# riscurino-1_0.net
KiCad netlist of a schematic drawn in EAGLE
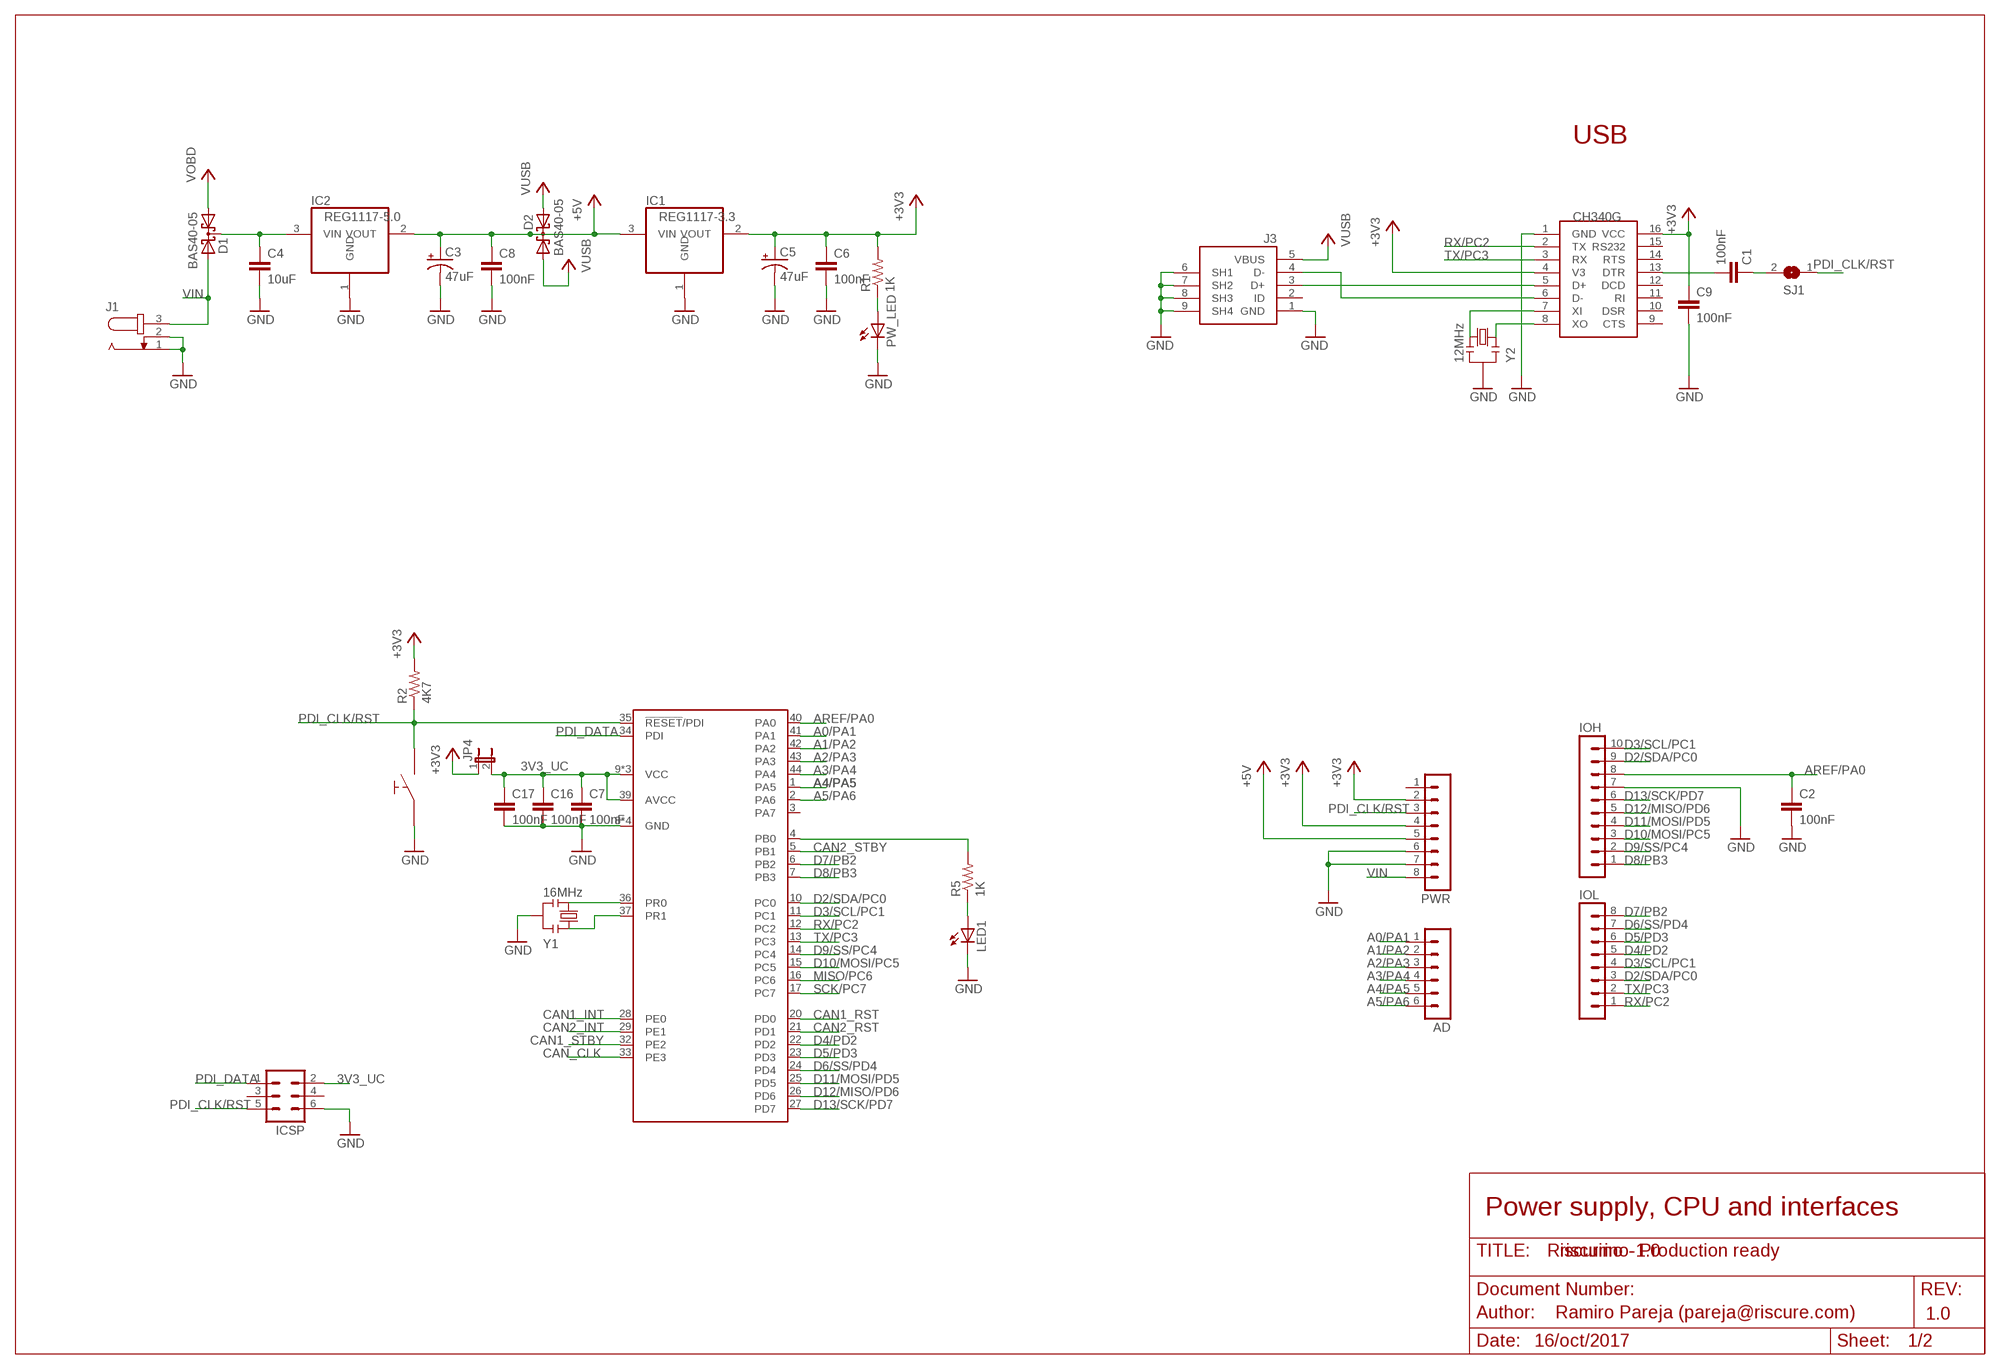
[diagram p0: schematic, sheet 1]
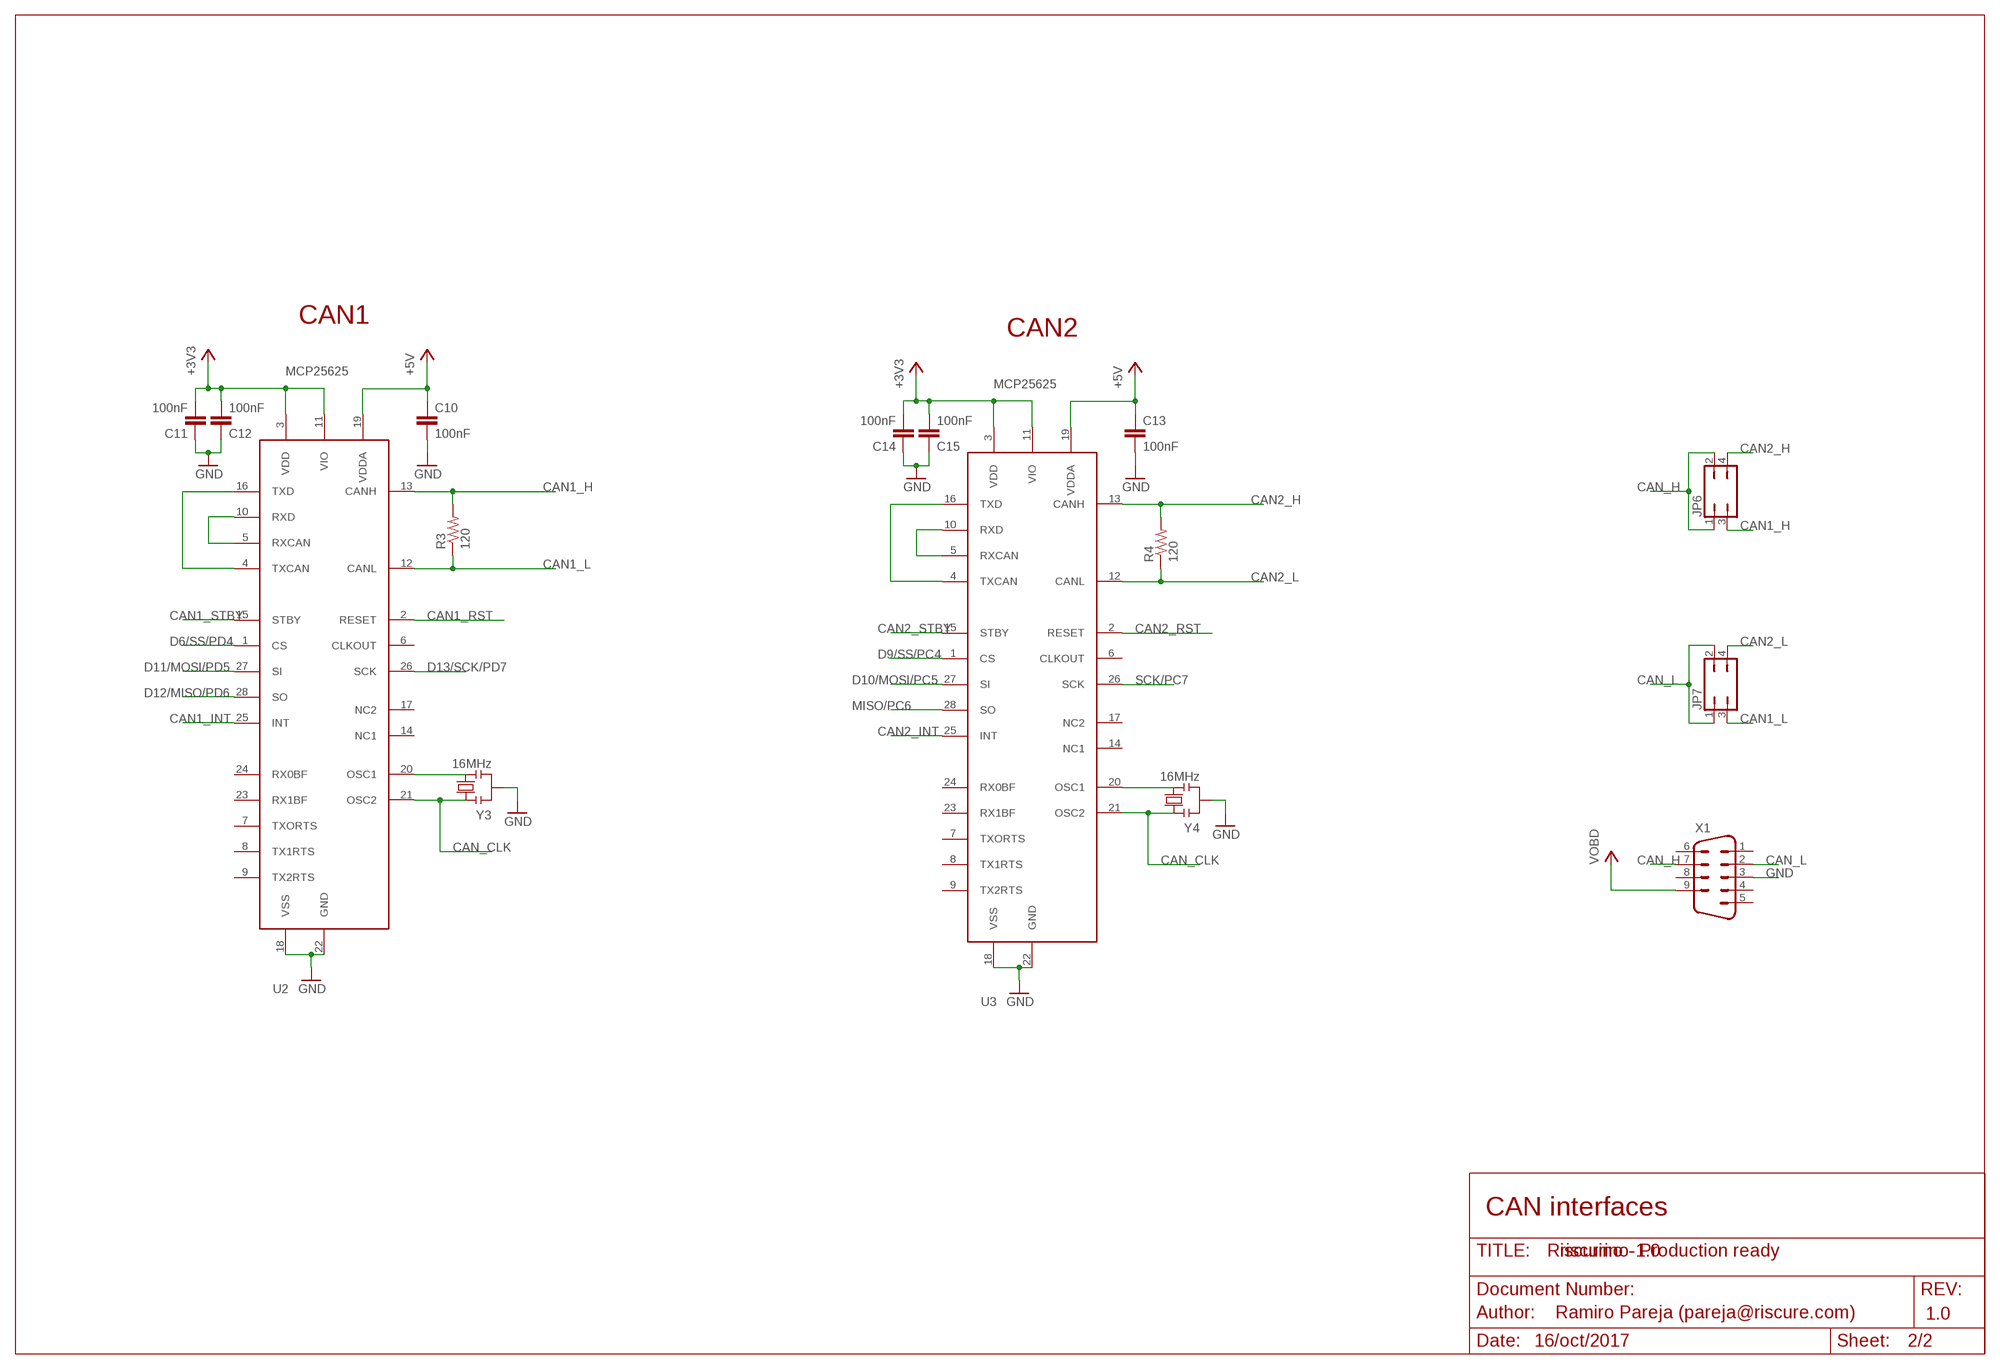
[diagram p1: schematic, sheet 2]

(export (version "E")
  (design (tool "Eeschema 10.0.6"))
  (components
    (comp (ref "AD")
      (value "MA06-1")
      (footprint "eagle-import:MA06-1")
      (libsource (lib "eagle-import") (part "MA06-1"))
    )
    (comp (ref "C1")
      (value "100nF")
      (footprint "eagle-import:C0805")
      (libsource (lib "eagle-import") (part "C-EUC0805"))
    )
    (comp (ref "C2")
      (value "100nF")
      (footprint "eagle-import:C0805")
      (libsource (lib "eagle-import") (part "C-EUC0805"))
    )
    (comp (ref "C3")
      (value "47uF")
      (footprint "eagle-import:PANASONIC_C")
      (libsource (lib "eagle-import") (part "CPOL-USC"))
    )
    (comp (ref "C4")
      (value "10uF")
      (footprint "eagle-import:C0805")
      (libsource (lib "eagle-import") (part "C-EUC0805"))
    )
    (comp (ref "C5")
      (value "47uF")
      (footprint "eagle-import:PANASONIC_C")
      (libsource (lib "eagle-import") (part "CPOL-USC"))
    )
    (comp (ref "C6")
      (value "100nF")
      (footprint "eagle-import:C0805")
      (libsource (lib "eagle-import") (part "C-EUC0805"))
    )
    (comp (ref "C7")
      (value "100nF")
      (footprint "eagle-import:C0805")
      (libsource (lib "eagle-import") (part "C-EUC0805"))
    )
    (comp (ref "C8")
      (value "100nF")
      (footprint "eagle-import:C0805")
      (libsource (lib "eagle-import") (part "C-EUC0805"))
    )
    (comp (ref "C9")
      (value "100nF")
      (footprint "eagle-import:C0805")
      (libsource (lib "eagle-import") (part "C-EUC0805"))
    )
    (comp (ref "C16")
      (value "100nF")
      (footprint "eagle-import:C0805")
      (libsource (lib "eagle-import") (part "C-EUC0805"))
    )
    (comp (ref "C17")
      (value "100nF")
      (footprint "eagle-import:C0805")
      (libsource (lib "eagle-import") (part "C-EUC0805"))
    )
    (comp (ref "D1")
      (value "BAS40-05")
      (footprint "eagle-import:SOT23")
      (libsource (lib "eagle-import") (part "BAS40-05"))
    )
    (comp (ref "D2")
      (value "BAS40-05")
      (footprint "eagle-import:SOT23")
      (libsource (lib "eagle-import") (part "BAS40-05"))
    )
    (comp (ref "IC1")
      (value "REG1117-3.3")
      (footprint "eagle-import:SOT223")
      (fields (field (name "MPN") "REG1117"))
      (libsource (lib "eagle-import") (part "REG1117"))
    )
    (comp (ref "IC2")
      (value "REG1117-5.0")
      (footprint "eagle-import:SOT223")
      (fields (field (name "MPN") "REG1117"))
      (libsource (lib "eagle-import") (part "REG1117"))
    )
    (comp (ref "ICSP")
      (value "MA03-2")
      (footprint "eagle-import:MA03-2")
      (libsource (lib "eagle-import") (part "MA03-2"))
    )
    (comp (ref "IOH")
      (value "MA10-1")
      (footprint "eagle-import:MA10-1")
      (libsource (lib "eagle-import") (part "MA10-1"))
    )
    (comp (ref "IOL")
      (value "MA08-1")
      (footprint "eagle-import:MA08-1")
      (libsource (lib "eagle-import") (part "MA08-1"))
    )
    (comp (ref "J1")
      (value "JACK-PLUG0")
      (footprint "eagle-import:SPC4077")
      (libsource (lib "eagle-import") (part "JACK-PLUG0"))
    )
    (comp (ref "J3")
      (value "0219_14850")
      (footprint "eagle-import:USB-MINI-B_2")
      (fields (field (name "PART_NUMBER") "14850"))
      (libsource (lib "eagle-import") (part "0219_14850"))
    )
    (comp (ref "JP4")
      (value "JP1E")
      (footprint "eagle-import:JP1")
      (libsource (lib "eagle-import") (part "JP1E"))
    )
    (comp (ref "LED1")
      (value "LEDCHIPLED_0805")
      (footprint "eagle-import:CHIPLED_0805")
      (libsource (lib "eagle-import") (part "LEDCHIPLED_0805"))
    )
    (comp (ref "PWR")
      (value "MA08-1")
      (footprint "eagle-import:MA08-1")
      (libsource (lib "eagle-import") (part "MA08-1"))
    )
    (comp (ref "PW_LED")
      (value "LEDCHIPLED_0805")
      (footprint "eagle-import:CHIPLED_0805")
      (libsource (lib "eagle-import") (part "LEDCHIPLED_0805"))
    )
    (comp (ref "R1")
      (value "1K")
      (footprint "eagle-import:R0805")
      (libsource (lib "eagle-import") (part "R-US_R0805"))
    )
    (comp (ref "R2")
      (value "4K7")
      (footprint "eagle-import:R0805")
      (libsource (lib "eagle-import") (part "R-US_R0805"))
    )
    (comp (ref "R5")
      (value "1K")
      (footprint "eagle-import:R0805")
      (libsource (lib "eagle-import") (part "R-US_R0805"))
    )
    (comp (ref "SJ1") (value "SJ") (footprint "eagle-import:SJ") (libsource (lib "eagle-import") (part "SJ")))
    (comp (ref "U$1")
      (value "SWITCH_3X6_BIG")
      (footprint "eagle-import:SWITCH_3X6_BIG")
      (libsource (lib "eagle-import") (part "SWITCH_3X6_BIG"))
    )
    (comp (ref "U1")
      (value "ATXMEGA128A4U-AU")
      (footprint "eagle-import:TQFP-44A-44")
      (libsource (lib "eagle-import") (part "ATXMEGA128A4U-AU"))
    )
    (comp (ref "U4")
      (value "CH340G")
      (footprint "eagle-import:SOIC16")
      (libsource (lib "eagle-import") (part "CH340G"))
    )
    (comp (ref "Y1")
      (value "16MHz")
      (footprint "eagle-import:RESONATOR")
      (fields (field (name "PART_NUMBER") "CSTCE16M0V53-R0"))
      (libsource (lib "eagle-import") (part "0011_CSTCE16M0V53-R0"))
    )
    (comp (ref "Y2")
      (value "12MHz")
      (footprint "eagle-import:RESONATOR")
      (fields (field (name "PART_NUMBER") "CSTCE16M0V53-R0"))
      (libsource (lib "eagle-import") (part "0011_CSTCE16M0V53-R0"))
    )
    (comp (ref "C10")
      (value "100nF")
      (footprint "eagle-import:C0805")
      (libsource (lib "eagle-import") (part "C-EUC0805"))
    )
    (comp (ref "C11")
      (value "100nF")
      (footprint "eagle-import:C0805")
      (libsource (lib "eagle-import") (part "C-EUC0805"))
    )
    (comp (ref "C12")
      (value "100nF")
      (footprint "eagle-import:C0805")
      (libsource (lib "eagle-import") (part "C-EUC0805"))
    )
    (comp (ref "C13")
      (value "100nF")
      (footprint "eagle-import:C0805")
      (libsource (lib "eagle-import") (part "C-EUC0805"))
    )
    (comp (ref "C14")
      (value "100nF")
      (footprint "eagle-import:C0805")
      (libsource (lib "eagle-import") (part "C-EUC0805"))
    )
    (comp (ref "C15")
      (value "100nF")
      (footprint "eagle-import:C0805")
      (libsource (lib "eagle-import") (part "C-EUC0805"))
    )
    (comp (ref "JP6")
      (value "JP2Q")
      (footprint "eagle-import:JP2Q")
      (libsource (lib "eagle-import") (part "JP2Q"))
    )
    (comp (ref "JP7")
      (value "JP2Q")
      (footprint "eagle-import:JP2Q")
      (libsource (lib "eagle-import") (part "JP2Q"))
    )
    (comp (ref "R3")
      (value "120")
      (footprint "eagle-import:R0805")
      (libsource (lib "eagle-import") (part "R-US_R0805"))
    )
    (comp (ref "R4")
      (value "120")
      (footprint "eagle-import:R0805")
      (libsource (lib "eagle-import") (part "R-US_R0805"))
    )
    (comp (ref "U2")
      (value "MCP25625")
      (footprint "eagle-import:QFN28")
      (libsource (lib "eagle-import") (part "MCP25625"))
    )
    (comp (ref "U3")
      (value "MCP25625")
      (footprint "eagle-import:QFN28")
      (libsource (lib "eagle-import") (part "MCP25625"))
    )
    (comp (ref "X1")
      (value "M09HP")
      (footprint "eagle-import:M09HP")
      (libsource (lib "eagle-import") (part "M09HP"))
    )
    (comp (ref "Y3")
      (value "16MHz")
      (footprint "eagle-import:RESONATOR")
      (fields (field (name "PART_NUMBER") "CSTCE16M0V53-R0"))
      (libsource (lib "eagle-import") (part "0011_CSTCE16M0V53-R0"))
    )
    (comp (ref "Y4")
      (value "16MHz")
      (footprint "eagle-import:RESONATOR")
      (fields (field (name "PART_NUMBER") "CSTCE16M0V53-R0"))
      (libsource (lib "eagle-import") (part "0011_CSTCE16M0V53-R0"))
    )
  )
  (nets
    (net (code "1") (name "+3V3") (class "Default")
      (node (ref "C11") (pin "2") (pinfunction "2_2") (pintype "passive"))
      (node (ref "C12") (pin "2") (pinfunction "2_2") (pintype "passive"))
      (node (ref "C14") (pin "2") (pinfunction "2_2") (pintype "passive"))
      (node (ref "C15") (pin "2") (pinfunction "2_2") (pintype "passive"))
      (node (ref "C5") (pin "+") (pinfunction "+_+") (pintype "passive"))
      (node (ref "C6") (pin "1") (pinfunction "1_1") (pintype "passive"))
      (node (ref "C9") (pin "1") (pinfunction "1_1") (pintype "passive"))
      (node (ref "IC1") (pin "2") (pinfunction "VOUT_2") (pintype "output"))
      (node (ref "JP4") (pin "1") (pinfunction "1_1") (pintype "passive"))
      (node (ref "PWR") (pin "2") (pinfunction "2_2") (pintype "passive"))
      (node (ref "PWR") (pin "4") (pinfunction "4_4") (pintype "passive"))
      (node (ref "R1") (pin "2") (pinfunction "2_2") (pintype "passive"))
      (node (ref "R2") (pin "2") (pinfunction "2_2") (pintype "passive"))
      (node (ref "U2") (pin "11") (pinfunction "VIO_11") (pintype "bidirectional"))
      (node (ref "U2") (pin "3") (pinfunction "VDD_3") (pintype "power_in"))
      (node (ref "U3") (pin "11") (pinfunction "VIO_11") (pintype "bidirectional"))
      (node (ref "U3") (pin "3") (pinfunction "VDD_3") (pintype "power_in"))
      (node (ref "U4") (pin "16") (pinfunction "VCC_16") (pintype "bidirectional"))
      (node (ref "U4") (pin "4") (pinfunction "V3_4") (pintype "bidirectional"))
    )
    (net (code "2") (name "+5V") (class "Default")
      (node (ref "C10") (pin "1") (pinfunction "1_1") (pintype "passive"))
      (node (ref "C13") (pin "1") (pinfunction "1_1") (pintype "passive"))
      (node (ref "C3") (pin "+") (pinfunction "+_+") (pintype "passive"))
      (node (ref "C8") (pin "1") (pinfunction "1_1") (pintype "passive"))
      (node (ref "D2") (pin "3") (pinfunction "C_3") (pintype "passive"))
      (node (ref "IC1") (pin "3") (pinfunction "VIN_3") (pintype "input"))
      (node (ref "IC2") (pin "2") (pinfunction "VOUT_2") (pintype "output"))
      (node (ref "PWR") (pin "5") (pinfunction "5_5") (pintype "passive"))
      (node (ref "U2") (pin "19") (pinfunction "VDDA_19") (pintype "power_in"))
      (node (ref "U3") (pin "19") (pinfunction "VDDA_19") (pintype "power_in"))
    )
    (net (code "3") (name "3V3_UC") (class "Default")
      (node (ref "C16") (pin "1") (pinfunction "1_1") (pintype "passive"))
      (node (ref "C17") (pin "1") (pinfunction "1_1") (pintype "passive"))
      (node (ref "C7") (pin "1") (pinfunction "1_1") (pintype "passive"))
      (node (ref "ICSP") (pin "2") (pinfunction "2_2") (pintype "passive"))
      (node (ref "JP4") (pin "2") (pinfunction "2_2") (pintype "passive"))
      (node (ref "U1") (pin "19") (pinfunction "VCC_19") (pintype "power_in"))
      (node (ref "U1") (pin "31") (pinfunction "VCC_31") (pintype "power_in"))
      (node (ref "U1") (pin "39") (pinfunction "AVCC_39") (pintype "power_in"))
      (node (ref "U1") (pin "9") (pinfunction "VCC_9") (pintype "power_in"))
    )
    (net (code "4") (name "A0{slash}PA1") (class "Default")
      (node (ref "AD") (pin "1") (pinfunction "1_1") (pintype "passive"))
      (node (ref "U1") (pin "41") (pinfunction "PA1_41") (pintype "bidirectional"))
    )
    (net (code "5") (name "A1{slash}PA2") (class "Default")
      (node (ref "AD") (pin "2") (pinfunction "2_2") (pintype "passive"))
      (node (ref "U1") (pin "42") (pinfunction "PA2_42") (pintype "bidirectional"))
    )
    (net (code "6") (name "A2{slash}PA3") (class "Default")
      (node (ref "AD") (pin "3") (pinfunction "3_3") (pintype "passive"))
      (node (ref "U1") (pin "43") (pinfunction "PA3_43") (pintype "bidirectional"))
    )
    (net (code "7") (name "A3{slash}PA4") (class "Default")
      (node (ref "AD") (pin "4") (pinfunction "4_4") (pintype "passive"))
      (node (ref "U1") (pin "44") (pinfunction "PA4_44") (pintype "bidirectional"))
    )
    (net (code "8") (name "A4{slash}PA5") (class "Default")
      (node (ref "AD") (pin "5") (pinfunction "5_5") (pintype "passive"))
      (node (ref "U1") (pin "1") (pinfunction "PA5_1") (pintype "bidirectional"))
    )
    (net (code "9") (name "A5{slash}PA6") (class "Default")
      (node (ref "AD") (pin "6") (pinfunction "6_6") (pintype "passive"))
      (node (ref "U1") (pin "2") (pinfunction "PA6_2") (pintype "bidirectional"))
    )
    (net (code "10") (name "AREF{slash}PA0") (class "Default")
      (node (ref "C2") (pin "1") (pinfunction "1_1") (pintype "passive"))
      (node (ref "IOH") (pin "8") (pinfunction "8_8") (pintype "passive"))
      (node (ref "U1") (pin "40") (pinfunction "PA0_40") (pintype "bidirectional"))
    )
    (net (code "11") (name "CAN1_H") (class "Default")
      (node (ref "JP6") (pin "3") (pinfunction "3_3") (pintype "passive"))
      (node (ref "R3") (pin "2") (pinfunction "2_2") (pintype "passive"))
      (node (ref "U2") (pin "13") (pinfunction "CANH_13") (pintype "bidirectional"))
    )
    (net (code "12") (name "CAN1_INT") (class "Default")
      (node (ref "U1") (pin "28") (pinfunction "PE0_28") (pintype "bidirectional"))
      (node (ref "U2") (pin "25") (pinfunction "INT_25") (pintype "bidirectional"))
    )
    (net (code "13") (name "CAN1_L") (class "Default")
      (node (ref "JP7") (pin "3") (pinfunction "3_3") (pintype "passive"))
      (node (ref "R3") (pin "1") (pinfunction "1_1") (pintype "passive"))
      (node (ref "U2") (pin "12") (pinfunction "CANL_12") (pintype "bidirectional"))
    )
    (net (code "14") (name "CAN1_RST") (class "Default")
      (node (ref "U1") (pin "20") (pinfunction "PD0_20") (pintype "bidirectional"))
      (node (ref "U2") (pin "2") (pinfunction "RESET_2") (pintype "bidirectional"))
    )
    (net (code "15") (name "CAN1_STBY") (class "Default")
      (node (ref "U1") (pin "32") (pinfunction "PE2_32") (pintype "bidirectional"))
      (node (ref "U2") (pin "15") (pinfunction "STBY_15") (pintype "bidirectional"))
    )
    (net (code "16") (name "CAN2_H") (class "Default")
      (node (ref "JP6") (pin "4") (pinfunction "4_4") (pintype "passive"))
      (node (ref "R4") (pin "2") (pinfunction "2_2") (pintype "passive"))
      (node (ref "U3") (pin "13") (pinfunction "CANH_13") (pintype "bidirectional"))
    )
    (net (code "17") (name "CAN2_INT") (class "Default")
      (node (ref "U1") (pin "29") (pinfunction "PE1_29") (pintype "bidirectional"))
      (node (ref "U3") (pin "25") (pinfunction "INT_25") (pintype "bidirectional"))
    )
    (net (code "18") (name "CAN2_L") (class "Default")
      (node (ref "JP7") (pin "4") (pinfunction "4_4") (pintype "passive"))
      (node (ref "R4") (pin "1") (pinfunction "1_1") (pintype "passive"))
      (node (ref "U3") (pin "12") (pinfunction "CANL_12") (pintype "bidirectional"))
    )
    (net (code "19") (name "CAN2_RST") (class "Default")
      (node (ref "U1") (pin "21") (pinfunction "PD1_21") (pintype "bidirectional"))
      (node (ref "U3") (pin "2") (pinfunction "RESET_2") (pintype "bidirectional"))
    )
    (net (code "20") (name "CAN2_STBY") (class "Default")
      (node (ref "U1") (pin "5") (pinfunction "PB1_5") (pintype "bidirectional"))
      (node (ref "U3") (pin "15") (pinfunction "STBY_15") (pintype "bidirectional"))
    )
    (net (code "21") (name "CAN_CLK") (class "Default")
      (node (ref "U1") (pin "33") (pinfunction "PE3_33") (pintype "bidirectional"))
      (node (ref "U2") (pin "21") (pinfunction "OSC2_21") (pintype "bidirectional"))
      (node (ref "U3") (pin "21") (pinfunction "OSC2_21") (pintype "bidirectional"))
      (node (ref "Y3") (pin "1") (pinfunction "1_1") (pintype "passive"))
      (node (ref "Y4") (pin "1") (pinfunction "1_1") (pintype "passive"))
    )
    (net (code "22") (name "CAN_H") (class "Default")
      (node (ref "JP6") (pin "1") (pinfunction "1_1") (pintype "passive"))
      (node (ref "JP6") (pin "2") (pinfunction "2_2") (pintype "passive"))
      (node (ref "X1") (pin "7") (pinfunction "7_7") (pintype "passive"))
    )
    (net (code "23") (name "CAN_L") (class "Default")
      (node (ref "JP7") (pin "1") (pinfunction "1_1") (pintype "passive"))
      (node (ref "JP7") (pin "2") (pinfunction "2_2") (pintype "passive"))
      (node (ref "X1") (pin "2") (pinfunction "2_2") (pintype "passive"))
    )
    (net (code "24") (name "D2{slash}SDA{slash}PC0") (class "Default")
      (node (ref "IOH") (pin "9") (pinfunction "9_9") (pintype "passive"))
      (node (ref "IOL") (pin "3") (pinfunction "3_3") (pintype "passive"))
      (node (ref "U1") (pin "10") (pinfunction "PC0_10") (pintype "bidirectional"))
    )
    (net (code "25") (name "D3{slash}SCL{slash}PC1") (class "Default")
      (node (ref "IOH") (pin "10") (pinfunction "10_10") (pintype "passive"))
      (node (ref "IOL") (pin "4") (pinfunction "4_4") (pintype "passive"))
      (node (ref "U1") (pin "11") (pinfunction "PC1_11") (pintype "bidirectional"))
    )
    (net (code "26") (name "D4{slash}PD2") (class "Default")
      (node (ref "IOL") (pin "5") (pinfunction "5_5") (pintype "passive"))
      (node (ref "U1") (pin "22") (pinfunction "PD2_22") (pintype "bidirectional"))
    )
    (net (code "27") (name "D5{slash}PD3") (class "Default")
      (node (ref "IOL") (pin "6") (pinfunction "6_6") (pintype "passive"))
      (node (ref "U1") (pin "23") (pinfunction "PD3_23") (pintype "bidirectional"))
    )
    (net (code "28") (name "D6{slash}SS{slash}PD4") (class "Default")
      (node (ref "IOL") (pin "7") (pinfunction "7_7") (pintype "passive"))
      (node (ref "U1") (pin "24") (pinfunction "PD4_24") (pintype "bidirectional"))
      (node (ref "U2") (pin "1") (pinfunction "CS_1") (pintype "bidirectional"))
    )
    (net (code "29") (name "D7{slash}PB2") (class "Default")
      (node (ref "IOL") (pin "8") (pinfunction "8_8") (pintype "passive"))
      (node (ref "U1") (pin "6") (pinfunction "PB2_6") (pintype "bidirectional"))
    )
    (net (code "30") (name "D8{slash}PB3") (class "Default")
      (node (ref "IOH") (pin "1") (pinfunction "1_1") (pintype "passive"))
      (node (ref "U1") (pin "7") (pinfunction "PB3_7") (pintype "bidirectional"))
    )
    (net (code "31") (name "D9{slash}SS{slash}PC4") (class "Default")
      (node (ref "IOH") (pin "2") (pinfunction "2_2") (pintype "passive"))
      (node (ref "U1") (pin "14") (pinfunction "PC4_14") (pintype "bidirectional"))
      (node (ref "U3") (pin "1") (pinfunction "CS_1") (pintype "bidirectional"))
    )
    (net (code "32") (name "D10{slash}MOSI{slash}PC5") (class "Default")
      (node (ref "IOH") (pin "3") (pinfunction "3_3") (pintype "passive"))
      (node (ref "U1") (pin "15") (pinfunction "PC5_15") (pintype "bidirectional"))
      (node (ref "U3") (pin "27") (pinfunction "SI_27") (pintype "bidirectional"))
    )
    (net (code "33") (name "D11{slash}MOSI{slash}PD5") (class "Default")
      (node (ref "IOH") (pin "4") (pinfunction "4_4") (pintype "passive"))
      (node (ref "U1") (pin "25") (pinfunction "PD5_25") (pintype "bidirectional"))
      (node (ref "U2") (pin "27") (pinfunction "SI_27") (pintype "bidirectional"))
    )
    (net (code "34") (name "D12{slash}MISO{slash}PD6") (class "Default")
      (node (ref "IOH") (pin "5") (pinfunction "5_5") (pintype "passive"))
      (node (ref "U1") (pin "26") (pinfunction "PD6_26") (pintype "bidirectional"))
      (node (ref "U2") (pin "28") (pinfunction "SO_28") (pintype "bidirectional"))
    )
    (net (code "35") (name "D13{slash}SCK{slash}PD7") (class "Default")
      (node (ref "IOH") (pin "6") (pinfunction "6_6") (pintype "passive"))
      (node (ref "U1") (pin "27") (pinfunction "PD7_27") (pintype "bidirectional"))
      (node (ref "U2") (pin "26") (pinfunction "SCK_26") (pintype "bidirectional"))
    )
    (net (code "36") (name "GND") (class "Default")
      (node (ref "C10") (pin "2") (pinfunction "2_2") (pintype "passive"))
      (node (ref "C11") (pin "1") (pinfunction "1_1") (pintype "passive"))
      (node (ref "C12") (pin "1") (pinfunction "1_1") (pintype "passive"))
      (node (ref "C13") (pin "2") (pinfunction "2_2") (pintype "passive"))
      (node (ref "C14") (pin "1") (pinfunction "1_1") (pintype "passive"))
      (node (ref "C15") (pin "1") (pinfunction "1_1") (pintype "passive"))
      (node (ref "C16") (pin "2") (pinfunction "2_2") (pintype "passive"))
      (node (ref "C17") (pin "2") (pinfunction "2_2") (pintype "passive"))
      (node (ref "C2") (pin "2") (pinfunction "2_2") (pintype "passive"))
      (node (ref "C3") (pin "-") (pinfunction "-_-") (pintype "passive"))
      (node (ref "C4") (pin "2") (pinfunction "2_2") (pintype "passive"))
      (node (ref "C5") (pin "-") (pinfunction "-_-") (pintype "passive"))
      (node (ref "C6") (pin "2") (pinfunction "2_2") (pintype "passive"))
      (node (ref "C7") (pin "2") (pinfunction "2_2") (pintype "passive"))
      (node (ref "C8") (pin "2") (pinfunction "2_2") (pintype "passive"))
      (node (ref "C9") (pin "2") (pinfunction "2_2") (pintype "passive"))
      (node (ref "IC1") (pin "1") (pinfunction "GND_1") (pintype "power_in"))
      (node (ref "IC2") (pin "1") (pinfunction "GND_1") (pintype "power_in"))
      (node (ref "ICSP") (pin "6") (pinfunction "6_6") (pintype "passive"))
      (node (ref "IOH") (pin "7") (pinfunction "7_7") (pintype "passive"))
      (node (ref "J1") (pin "1") (pinfunction "1_1") (pintype "passive"))
      (node (ref "J1") (pin "2") (pinfunction "2_2") (pintype "passive"))
      (node (ref "J3") (pin "1") (pinfunction "GND_1") (pintype "passive"))
      (node (ref "J3") (pin "6") (pinfunction "SH1_6") (pintype "passive"))
      (node (ref "J3") (pin "7") (pinfunction "SH2_7") (pintype "passive"))
      (node (ref "J3") (pin "8") (pinfunction "SH3_8") (pintype "passive"))
      (node (ref "J3") (pin "9") (pinfunction "SH4_9") (pintype "passive"))
      (node (ref "LED1") (pin "C") (pinfunction "C_C") (pintype "passive"))
      (node (ref "PWR") (pin "6") (pinfunction "6_6") (pintype "passive"))
      (node (ref "PWR") (pin "7") (pinfunction "7_7") (pintype "passive"))
      (node (ref "PW_LED") (pin "C") (pinfunction "C_C") (pintype "passive"))
      (node (ref "U$1") (pin "P$1") (pinfunction "P$1_P$1") (pintype "bidirectional"))
      (node (ref "U1") (pin "18") (pinfunction "GND_18") (pintype "power_in"))
      (node (ref "U1") (pin "30") (pinfunction "GND_30") (pintype "power_in"))
      (node (ref "U1") (pin "38") (pinfunction "GND_38") (pintype "power_in"))
      (node (ref "U1") (pin "8") (pinfunction "GND_8") (pintype "power_in"))
      (node (ref "U2") (pin "18") (pinfunction "VSS_18") (pintype "power_in"))
      (node (ref "U2") (pin "22") (pinfunction "GND_22") (pintype "power_in"))
      (node (ref "U3") (pin "18") (pinfunction "VSS_18") (pintype "power_in"))
      (node (ref "U3") (pin "22") (pinfunction "GND_22") (pintype "power_in"))
      (node (ref "U4") (pin "1") (pinfunction "GND_1") (pintype "bidirectional"))
      (node (ref "X1") (pin "3") (pinfunction "3_3") (pintype "passive"))
      (node (ref "Y1") (pin "2") (pinfunction "2_2") (pintype "passive"))
      (node (ref "Y2") (pin "2") (pinfunction "2_2") (pintype "passive"))
      (node (ref "Y3") (pin "2") (pinfunction "2_2") (pintype "passive"))
      (node (ref "Y4") (pin "2") (pinfunction "2_2") (pintype "passive"))
    )
    (net (code "37") (name "MISO{slash}PC6") (class "Default")
      (node (ref "U1") (pin "16") (pinfunction "PC6_16") (pintype "bidirectional"))
      (node (ref "U3") (pin "28") (pinfunction "SO_28") (pintype "bidirectional"))
    )
    (net (code "38") (name "Net-(C1-Pad1)") (class "Default")
      (node (ref "C1") (pin "1") (pinfunction "1_1") (pintype "passive"))
      (node (ref "SJ1") (pin "2") (pinfunction "2_2") (pintype "passive"))
    )
    (net (code "39") (name "Net-(D1-C)") (class "Default")
      (node (ref "C4") (pin "1") (pinfunction "1_1") (pintype "passive"))
      (node (ref "D1") (pin "3") (pinfunction "C_3") (pintype "passive"))
      (node (ref "IC2") (pin "3") (pinfunction "VIN_3") (pintype "input"))
    )
    (net (code "40") (name "Net-(J3-D+)") (class "Default")
      (node (ref "J3") (pin "3") (pinfunction "D+_3") (pintype "bidirectional"))
      (node (ref "U4") (pin "5") (pinfunction "D+_5") (pintype "bidirectional"))
    )
    (net (code "41") (name "Net-(J3-D-)") (class "Default")
      (node (ref "J3") (pin "4") (pinfunction "D-_4") (pintype "bidirectional"))
      (node (ref "U4") (pin "6") (pinfunction "D-_6") (pintype "bidirectional"))
    )
    (net (code "42") (name "Net-(LED1-PadA)") (class "Default")
      (node (ref "LED1") (pin "A") (pinfunction "A_A") (pintype "passive"))
      (node (ref "R5") (pin "1") (pinfunction "1_1") (pintype "passive"))
    )
    (net (code "43") (name "Net-(PW_LED-PadA)") (class "Default")
      (node (ref "PW_LED") (pin "A") (pinfunction "A_A") (pintype "passive"))
      (node (ref "R1") (pin "1") (pinfunction "1_1") (pintype "passive"))
    )
    (net (code "44") (name "Net-(U1-PB0)") (class "Default")
      (node (ref "R5") (pin "2") (pinfunction "2_2") (pintype "passive"))
      (node (ref "U1") (pin "4") (pinfunction "PB0_4") (pintype "bidirectional"))
    )
    (net (code "45") (name "Net-(U1-PR0)") (class "Default")
      (node (ref "U1") (pin "36") (pinfunction "PR0_36") (pintype "bidirectional"))
      (node (ref "Y1") (pin "3") (pinfunction "3_3") (pintype "passive"))
    )
    (net (code "46") (name "Net-(U1-PR1)") (class "Default")
      (node (ref "U1") (pin "37") (pinfunction "PR1_37") (pintype "bidirectional"))
      (node (ref "Y1") (pin "1") (pinfunction "1_1") (pintype "passive"))
    )
    (net (code "47") (name "Net-(U2-OSC1)") (class "Default")
      (node (ref "U2") (pin "20") (pinfunction "OSC1_20") (pintype "bidirectional"))
      (node (ref "Y3") (pin "3") (pinfunction "3_3") (pintype "passive"))
    )
    (net (code "48") (name "Net-(U2-RXCAN)") (class "Default")
      (node (ref "U2") (pin "10") (pinfunction "RXD_10") (pintype "bidirectional"))
      (node (ref "U2") (pin "5") (pinfunction "RXCAN_5") (pintype "bidirectional"))
    )
    (net (code "49") (name "Net-(U2-TXCAN)") (class "Default")
      (node (ref "U2") (pin "16") (pinfunction "TXD_16") (pintype "bidirectional"))
      (node (ref "U2") (pin "4") (pinfunction "TXCAN_4") (pintype "bidirectional"))
    )
    (net (code "50") (name "Net-(U3-OSC1)") (class "Default")
      (node (ref "U3") (pin "20") (pinfunction "OSC1_20") (pintype "bidirectional"))
      (node (ref "Y4") (pin "3") (pinfunction "3_3") (pintype "passive"))
    )
    (net (code "51") (name "Net-(U3-RXCAN)") (class "Default")
      (node (ref "U3") (pin "10") (pinfunction "RXD_10") (pintype "bidirectional"))
      (node (ref "U3") (pin "5") (pinfunction "RXCAN_5") (pintype "bidirectional"))
    )
    (net (code "52") (name "Net-(U3-TXCAN)") (class "Default")
      (node (ref "U3") (pin "16") (pinfunction "TXD_16") (pintype "bidirectional"))
      (node (ref "U3") (pin "4") (pinfunction "TXCAN_4") (pintype "bidirectional"))
    )
    (net (code "53") (name "Net-(U4-DTR)") (class "Default")
      (node (ref "C1") (pin "2") (pinfunction "2_2") (pintype "passive"))
      (node (ref "U4") (pin "13") (pinfunction "DTR_13") (pintype "bidirectional"))
    )
    (net (code "54") (name "Net-(U4-XI)") (class "Default")
      (node (ref "U4") (pin "7") (pinfunction "XI_7") (pintype "bidirectional"))
      (node (ref "Y2") (pin "3") (pinfunction "3_3") (pintype "passive"))
    )
    (net (code "55") (name "Net-(U4-XO)") (class "Default")
      (node (ref "U4") (pin "8") (pinfunction "XO_8") (pintype "bidirectional"))
      (node (ref "Y2") (pin "1") (pinfunction "1_1") (pintype "passive"))
    )
    (net (code "56") (name "PDI_CLK{slash}RST") (class "Default")
      (node (ref "ICSP") (pin "5") (pinfunction "5_5") (pintype "passive"))
      (node (ref "PWR") (pin "3") (pinfunction "3_3") (pintype "passive"))
      (node (ref "R2") (pin "1") (pinfunction "1_1") (pintype "passive"))
      (node (ref "SJ1") (pin "1") (pinfunction "1_1") (pintype "passive"))
      (node (ref "U$1") (pin "P$2") (pinfunction "P$2_P$2") (pintype "bidirectional"))
      (node (ref "U1") (pin "35") (pinfunction "~{RESET}/PDI_35") (pintype "bidirectional"))
    )
    (net (code "57") (name "PDI_DATA") (class "Default")
      (node (ref "ICSP") (pin "1") (pinfunction "1_1") (pintype "passive"))
      (node (ref "U1") (pin "34") (pinfunction "PDI_34") (pintype "bidirectional"))
    )
    (net (code "58") (name "RX{slash}PC2") (class "Default")
      (node (ref "IOL") (pin "1") (pinfunction "1_1") (pintype "passive"))
      (node (ref "U1") (pin "12") (pinfunction "PC2_12") (pintype "bidirectional"))
      (node (ref "U4") (pin "2") (pinfunction "TX_2") (pintype "bidirectional"))
    )
    (net (code "59") (name "SCK{slash}PC7") (class "Default")
      (node (ref "U1") (pin "17") (pinfunction "PC7_17") (pintype "bidirectional"))
      (node (ref "U3") (pin "26") (pinfunction "SCK_26") (pintype "bidirectional"))
    )
    (net (code "60") (name "TX{slash}PC3") (class "Default")
      (node (ref "IOL") (pin "2") (pinfunction "2_2") (pintype "passive"))
      (node (ref "U1") (pin "13") (pinfunction "PC3_13") (pintype "bidirectional"))
      (node (ref "U4") (pin "3") (pinfunction "RX_3") (pintype "bidirectional"))
    )
    (net (code "61") (name "VIN") (class "Default")
      (node (ref "D1") (pin "2") (pinfunction "A2_2") (pintype "passive"))
      (node (ref "J1") (pin "3") (pinfunction "3_3") (pintype "passive"))
      (node (ref "PWR") (pin "8") (pinfunction "8_8") (pintype "passive"))
    )
    (net (code "62") (name "VOBD") (class "Default")
      (node (ref "D1") (pin "1") (pinfunction "A1_1") (pintype "passive"))
      (node (ref "X1") (pin "9") (pinfunction "9_9") (pintype "passive"))
    )
    (net (code "63") (name "VUSB") (class "Default")
      (node (ref "D2") (pin "1") (pinfunction "A1_1") (pintype "passive"))
      (node (ref "D2") (pin "2") (pinfunction "A2_2") (pintype "passive"))
      (node (ref "J3") (pin "5") (pinfunction "VBUS_5") (pintype "power_in"))
    )
    (net (code "64") (name "unconnected-(ICSP-Pad3)") (class "Default")
      (node (ref "ICSP") (pin "3") (pinfunction "3_3") (pintype "passive"))
    )
    (net (code "65") (name "unconnected-(ICSP-Pad4)") (class "Default")
      (node (ref "ICSP") (pin "4") (pinfunction "4_4") (pintype "passive"))
    )
    (net (code "66") (name "unconnected-(J3-ID-Pad2)") (class "Default")
      (node (ref "J3") (pin "2") (pinfunction "ID_2") (pintype "bidirectional"))
    )
    (net (code "67") (name "unconnected-(PWR-Pad1)") (class "Default")
      (node (ref "PWR") (pin "1") (pinfunction "1_1") (pintype "passive"))
    )
    (net (code "68") (name "unconnected-(U1-PA7-Pad3)") (class "Default")
      (node (ref "U1") (pin "3") (pinfunction "PA7_3") (pintype "bidirectional"))
    )
    (net (code "69") (name "unconnected-(U2-CLKOUT-Pad6)") (class "Default")
      (node (ref "U2") (pin "6") (pinfunction "CLKOUT_6") (pintype "bidirectional"))
    )
    (net (code "70") (name "unconnected-(U2-NC1-Pad14)") (class "Default")
      (node (ref "U2") (pin "14") (pinfunction "NC1_14") (pintype "bidirectional"))
    )
    (net (code "71") (name "unconnected-(U2-NC2-Pad17)") (class "Default")
      (node (ref "U2") (pin "17") (pinfunction "NC2_17") (pintype "bidirectional"))
    )
    (net (code "72") (name "unconnected-(U2-RX0BF-Pad24)") (class "Default")
      (node (ref "U2") (pin "24") (pinfunction "RX0BF_24") (pintype "bidirectional"))
    )
    (net (code "73") (name "unconnected-(U2-RX1BF-Pad23)") (class "Default")
      (node (ref "U2") (pin "23") (pinfunction "RX1BF_23") (pintype "bidirectional"))
    )
    (net (code "74") (name "unconnected-(U2-TX1RTS-Pad8)") (class "Default")
      (node (ref "U2") (pin "8") (pinfunction "TX1RTS_8") (pintype "bidirectional"))
    )
    (net (code "75") (name "unconnected-(U2-TX2RTS-Pad9)") (class "Default")
      (node (ref "U2") (pin "9") (pinfunction "TX2RTS_9") (pintype "bidirectional"))
    )
    (net (code "76") (name "unconnected-(U2-TXORTS-Pad7)") (class "Default")
      (node (ref "U2") (pin "7") (pinfunction "TXORTS_7") (pintype "bidirectional"))
    )
    (net (code "77") (name "unconnected-(U3-CLKOUT-Pad6)") (class "Default")
      (node (ref "U3") (pin "6") (pinfunction "CLKOUT_6") (pintype "bidirectional"))
    )
    (net (code "78") (name "unconnected-(U3-NC1-Pad14)") (class "Default")
      (node (ref "U3") (pin "14") (pinfunction "NC1_14") (pintype "bidirectional"))
    )
    (net (code "79") (name "unconnected-(U3-NC2-Pad17)") (class "Default")
      (node (ref "U3") (pin "17") (pinfunction "NC2_17") (pintype "bidirectional"))
    )
    (net (code "80") (name "unconnected-(U3-RX0BF-Pad24)") (class "Default")
      (node (ref "U3") (pin "24") (pinfunction "RX0BF_24") (pintype "bidirectional"))
    )
    (net (code "81") (name "unconnected-(U3-RX1BF-Pad23)") (class "Default")
      (node (ref "U3") (pin "23") (pinfunction "RX1BF_23") (pintype "bidirectional"))
    )
    (net (code "82") (name "unconnected-(U3-TX1RTS-Pad8)") (class "Default")
      (node (ref "U3") (pin "8") (pinfunction "TX1RTS_8") (pintype "bidirectional"))
    )
    (net (code "83") (name "unconnected-(U3-TX2RTS-Pad9)") (class "Default")
      (node (ref "U3") (pin "9") (pinfunction "TX2RTS_9") (pintype "bidirectional"))
    )
    (net (code "84") (name "unconnected-(U3-TXORTS-Pad7)") (class "Default")
      (node (ref "U3") (pin "7") (pinfunction "TXORTS_7") (pintype "bidirectional"))
    )
    (net (code "85") (name "unconnected-(U4-CTS-Pad9)") (class "Default")
      (node (ref "U4") (pin "9") (pinfunction "CTS_9") (pintype "bidirectional"))
    )
    (net (code "86") (name "unconnected-(U4-DCD-Pad12)") (class "Default")
      (node (ref "U4") (pin "12") (pinfunction "DCD_12") (pintype "bidirectional"))
    )
    (net (code "87") (name "unconnected-(U4-DSR-Pad10)") (class "Default")
      (node (ref "U4") (pin "10") (pinfunction "DSR_10") (pintype "bidirectional"))
    )
    (net (code "88") (name "unconnected-(U4-RI-Pad11)") (class "Default")
      (node (ref "U4") (pin "11") (pinfunction "RI_11") (pintype "bidirectional"))
    )
    (net (code "89") (name "unconnected-(U4-RS232-Pad15)") (class "Default")
      (node (ref "U4") (pin "15") (pinfunction "RS232_15") (pintype "bidirectional"))
    )
    (net (code "90") (name "unconnected-(U4-RTS-Pad14)") (class "Default")
      (node (ref "U4") (pin "14") (pinfunction "RTS_14") (pintype "bidirectional"))
    )
    (net (code "91") (name "unconnected-(X1-Pad1)") (class "Default")
      (node (ref "X1") (pin "1") (pinfunction "1_1") (pintype "passive"))
    )
    (net (code "92") (name "unconnected-(X1-Pad4)") (class "Default")
      (node (ref "X1") (pin "4") (pinfunction "4_4") (pintype "passive"))
    )
    (net (code "93") (name "unconnected-(X1-Pad5)") (class "Default")
      (node (ref "X1") (pin "5") (pinfunction "5_5") (pintype "passive"))
    )
    (net (code "94") (name "unconnected-(X1-Pad6)") (class "Default")
      (node (ref "X1") (pin "6") (pinfunction "6_6") (pintype "passive"))
    )
    (net (code "95") (name "unconnected-(X1-Pad8)") (class "Default")
      (node (ref "X1") (pin "8") (pinfunction "8_8") (pintype "passive"))
    )
  )
)
